# soth-core.net
KiCad netlist of a schematic drawn in EAGLE
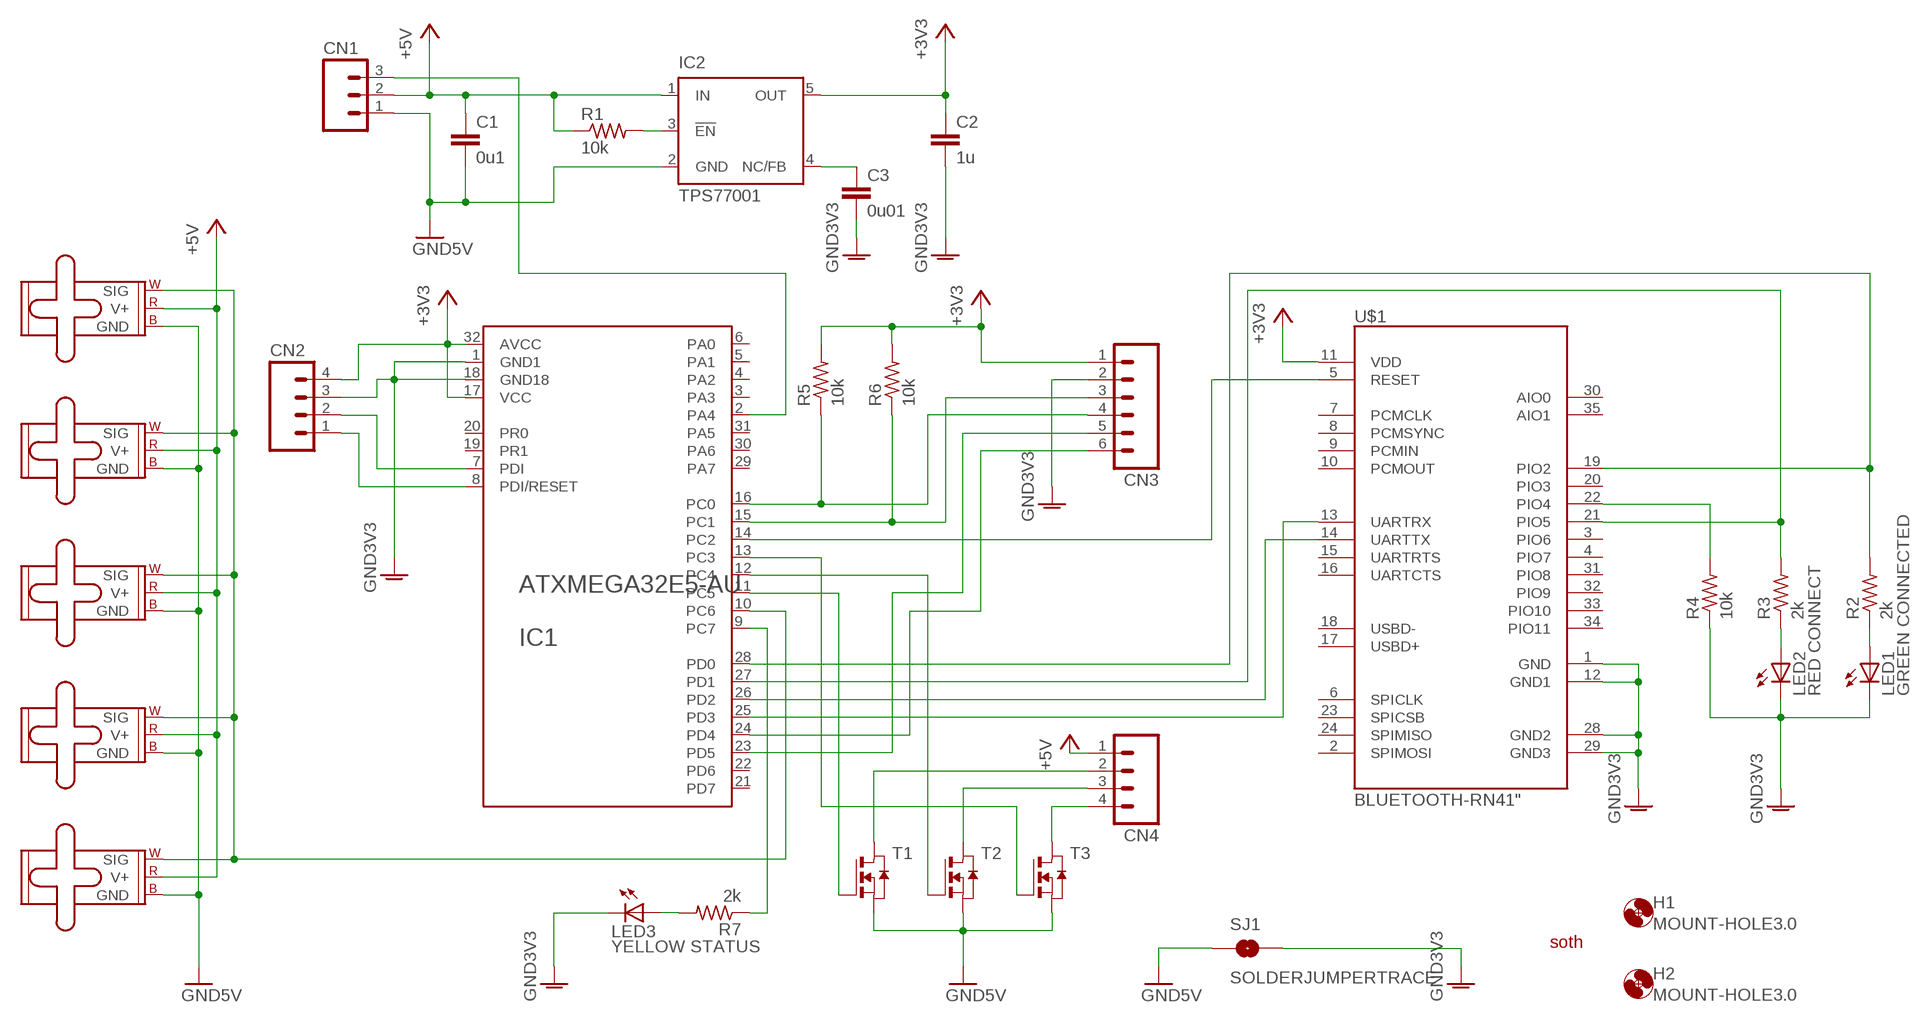
[diagram p0: schematic, sheet 1]

(export (version "E")
  (design (tool "Eeschema 10.0.6"))
  (components
    (comp (ref "C1")
      (value "0u1")
      (footprint "eagle-import:C1608")
      (libsource (lib "eagle-import") (part "C-EUC1608"))
    )
    (comp (ref "C2")
      (value "1u")
      (footprint "eagle-import:C1608")
      (libsource (lib "eagle-import") (part "C-EUC1608"))
    )
    (comp (ref "C3")
      (value "0u01")
      (footprint "eagle-import:C1608")
      (libsource (lib "eagle-import") (part "C-EUC1608"))
    )
    (comp (ref "CN1")
      (value "M03PTH")
      (footprint "eagle-import:1X03")
      (libsource (lib "eagle-import") (part "M03PTH"))
    )
    (comp (ref "CN2")
      (value "M04PTH")
      (footprint "eagle-import:1X04")
      (libsource (lib "eagle-import") (part "M04PTH"))
    )
    (comp (ref "CN3")
      (value "M06SILK_FEMALE_PTH")
      (footprint "eagle-import:1X06")
      (libsource (lib "eagle-import") (part "M06SILK_FEMALE_PTH"))
    )
    (comp (ref "CN4")
      (value "M04PTH")
      (footprint "eagle-import:1X04")
      (libsource (lib "eagle-import") (part "M04PTH"))
    )
    (comp (ref "H1")
      (value "MOUNT-HOLE3.0")
      (footprint "eagle-import:3,0")
      (libsource (lib "eagle-import") (part "MOUNT-HOLE3.0"))
    )
    (comp (ref "H2")
      (value "MOUNT-HOLE3.0")
      (footprint "eagle-import:3,0")
      (libsource (lib "eagle-import") (part "MOUNT-HOLE3.0"))
    )
    (comp (ref "IC1")
      (value "ATXMEGA32E5-AU")
      (footprint "eagle-import:TQFP32-08")
      (libsource (lib "eagle-import") (part "ATXMEGA32E5/16E5/8E5ATXMEGA32E5-AU"))
    )
    (comp (ref "IC2")
      (value "TPS77001")
      (footprint "eagle-import:SOT23-DBV")
      (fields (field (name "MF") "TEXAS INSTRUMENTS") (field (name "MPN") "TPS77001DBVT"))
      (libsource (lib "eagle-import") (part "TPS77001"))
    )
    (comp (ref "LED1")
      (value "GREEN CONNECTED")
      (footprint "eagle-import:CHIPLED_1206")
      (libsource (lib "eagle-import") (part "LEDCHIPLED_1206"))
    )
    (comp (ref "LED2")
      (value "RED CONNECT")
      (footprint "eagle-import:CHIPLED_1206")
      (libsource (lib "eagle-import") (part "LEDCHIPLED_1206"))
    )
    (comp (ref "LED3")
      (value "YELLOW STATUS")
      (footprint "eagle-import:CHIPLED_1206")
      (libsource (lib "eagle-import") (part "LEDCHIPLED_1206"))
    )
    (comp (ref "M1")
      (value "SMALL_SERVO")
      (footprint "eagle-import:1X03")
      (libsource (lib "eagle-import") (part "SMALL_SERVO"))
    )
    (comp (ref "M2")
      (value "SMALL_SERVO")
      (footprint "eagle-import:1X03")
      (libsource (lib "eagle-import") (part "SMALL_SERVO"))
    )
    (comp (ref "M3")
      (value "SMALL_SERVO")
      (footprint "eagle-import:1X03")
      (libsource (lib "eagle-import") (part "SMALL_SERVO"))
    )
    (comp (ref "M4")
      (value "SMALL_SERVO")
      (footprint "eagle-import:1X03")
      (libsource (lib "eagle-import") (part "SMALL_SERVO"))
    )
    (comp (ref "M5")
      (value "SMALL_SERVO")
      (footprint "eagle-import:1X03")
      (libsource (lib "eagle-import") (part "SMALL_SERVO"))
    )
    (comp (ref "R1")
      (value "10k")
      (footprint "eagle-import:R0603")
      (libsource (lib "eagle-import") (part "R-US_R0603"))
    )
    (comp (ref "R2")
      (value "2k")
      (footprint "eagle-import:R0603")
      (libsource (lib "eagle-import") (part "R-US_R0603"))
    )
    (comp (ref "R3")
      (value "2k")
      (footprint "eagle-import:R0603")
      (libsource (lib "eagle-import") (part "R-US_R0603"))
    )
    (comp (ref "R4")
      (value "10k")
      (footprint "eagle-import:R0603")
      (libsource (lib "eagle-import") (part "R-US_R0603"))
    )
    (comp (ref "R5")
      (value "10k")
      (footprint "eagle-import:R0603")
      (libsource (lib "eagle-import") (part "R-US_R0603"))
    )
    (comp (ref "R6")
      (value "10k")
      (footprint "eagle-import:R0603")
      (libsource (lib "eagle-import") (part "R-US_R0603"))
    )
    (comp (ref "R7")
      (value "2k")
      (footprint "eagle-import:R0603")
      (libsource (lib "eagle-import") (part "R-US_R0603"))
    )
    (comp (ref "SJ1")
      (value "SOLDERJUMPERTRACE")
      (footprint "eagle-import:SJ_2S-TRACE")
      (libsource (lib "eagle-import") (part "SOLDERJUMPERTRACE"))
    )
    (comp (ref "T1")
      (value "NMOSSOT23")
      (footprint "eagle-import:SOT-23")
      (libsource (lib "eagle-import") (part "NMOSSOT23"))
    )
    (comp (ref "T2")
      (value "NMOSSOT23")
      (footprint "eagle-import:SOT-23")
      (libsource (lib "eagle-import") (part "NMOSSOT23"))
    )
    (comp (ref "T3")
      (value "NMOSSOT23")
      (footprint "eagle-import:SOT-23")
      (libsource (lib "eagle-import") (part "NMOSSOT23"))
    )
    (comp (ref "U$1")
      (value "BLUETOOTH-RN41\"")
      (footprint "eagle-import:RN41")
      (libsource (lib "eagle-import") (part "BLUETOOTH-RN41{dblquote}"))
    )
    (comp (ref "U$2")
      (value "SOTH_LOGO")
      (footprint "eagle-import:SILK_LOGO")
      (libsource (lib "eagle-import") (part "SOTH_LOGO"))
    )
  )
  (nets
    (net (code "1") (name "+3V3") (class "Default")
      (node (ref "C2") (pin "1") (pinfunction "1_1") (pintype "passive"))
      (node (ref "CN2") (pin "4") (pinfunction "4_4") (pintype "passive"))
      (node (ref "CN3") (pin "1") (pinfunction "1_1") (pintype "passive"))
      (node (ref "IC1") (pin "17") (pinfunction "VCC_17") (pintype "power_in"))
      (node (ref "IC1") (pin "32") (pinfunction "AVCC_32") (pintype "power_in"))
      (node (ref "IC2") (pin "5") (pinfunction "OUT_5") (pintype "passive"))
      (node (ref "R5") (pin "2") (pinfunction "2_2") (pintype "passive"))
      (node (ref "R6") (pin "2") (pinfunction "2_2") (pintype "passive"))
      (node (ref "U$1") (pin "11") (pinfunction "VDD_11") (pintype "bidirectional"))
    )
    (net (code "2") (name "+5V") (class "Default")
      (node (ref "C1") (pin "1") (pinfunction "1_1") (pintype "passive"))
      (node (ref "CN1") (pin "2") (pinfunction "2_2") (pintype "passive"))
      (node (ref "CN4") (pin "1") (pinfunction "1_1") (pintype "passive"))
      (node (ref "IC2") (pin "1") (pinfunction "IN_1") (pintype "input"))
      (node (ref "M1") (pin "2") (pinfunction "V+_2") (pintype "bidirectional"))
      (node (ref "M2") (pin "2") (pinfunction "V+_2") (pintype "bidirectional"))
      (node (ref "M3") (pin "2") (pinfunction "V+_2") (pintype "bidirectional"))
      (node (ref "M4") (pin "2") (pinfunction "V+_2") (pintype "bidirectional"))
      (node (ref "M5") (pin "2") (pinfunction "V+_2") (pintype "bidirectional"))
      (node (ref "R1") (pin "1") (pinfunction "1_1") (pintype "passive"))
    )
    (net (code "3") (name "GND3V3") (class "Default")
      (node (ref "C2") (pin "2") (pinfunction "2_2") (pintype "passive"))
      (node (ref "C3") (pin "2") (pinfunction "2_2") (pintype "passive"))
      (node (ref "CN2") (pin "3") (pinfunction "3_3") (pintype "passive"))
      (node (ref "CN3") (pin "2") (pinfunction "2_2") (pintype "passive"))
      (node (ref "IC1") (pin "1") (pinfunction "GND1_1") (pintype "power_in"))
      (node (ref "IC1") (pin "18") (pinfunction "GND18_18") (pintype "power_in"))
      (node (ref "LED1") (pin "C") (pinfunction "C_C") (pintype "passive"))
      (node (ref "LED2") (pin "C") (pinfunction "C_C") (pintype "passive"))
      (node (ref "LED3") (pin "C") (pinfunction "C_C") (pintype "passive"))
      (node (ref "R4") (pin "1") (pinfunction "1_1") (pintype "passive"))
      (node (ref "SJ1") (pin "2") (pinfunction "2_2") (pintype "passive"))
      (node (ref "U$1") (pin "1") (pinfunction "GND_1") (pintype "bidirectional"))
      (node (ref "U$1") (pin "12") (pinfunction "GND1_12") (pintype "bidirectional"))
      (node (ref "U$1") (pin "28") (pinfunction "GND2_28") (pintype "bidirectional"))
      (node (ref "U$1") (pin "29") (pinfunction "GND3_29") (pintype "bidirectional"))
    )
    (net (code "4") (name "GND5V") (class "Default")
      (node (ref "C1") (pin "2") (pinfunction "2_2") (pintype "passive"))
      (node (ref "CN1") (pin "1") (pinfunction "1_1") (pintype "passive"))
      (node (ref "IC2") (pin "2") (pinfunction "GND_2") (pintype "power_in"))
      (node (ref "M1") (pin "3") (pinfunction "GND_3") (pintype "bidirectional"))
      (node (ref "M2") (pin "3") (pinfunction "GND_3") (pintype "bidirectional"))
      (node (ref "M3") (pin "3") (pinfunction "GND_3") (pintype "bidirectional"))
      (node (ref "M4") (pin "3") (pinfunction "GND_3") (pintype "bidirectional"))
      (node (ref "M5") (pin "3") (pinfunction "GND_3") (pintype "bidirectional"))
      (node (ref "SJ1") (pin "1") (pinfunction "1_1") (pintype "passive"))
      (node (ref "T1") (pin "2") (pinfunction "S_2") (pintype "passive"))
      (node (ref "T2") (pin "2") (pinfunction "S_2") (pintype "passive"))
      (node (ref "T3") (pin "2") (pinfunction "S_2") (pintype "passive"))
    )
    (net (code "5") (name "Net-(IC1-PA4)") (class "Default")
      (node (ref "CN1") (pin "3") (pinfunction "3_3") (pintype "passive"))
      (node (ref "IC1") (pin "2") (pinfunction "PA4_2") (pintype "bidirectional"))
    )
    (net (code "6") (name "Net-(IC1-PC0)") (class "Default")
      (node (ref "CN3") (pin "4") (pinfunction "4_4") (pintype "passive"))
      (node (ref "IC1") (pin "16") (pinfunction "PC0_16") (pintype "bidirectional"))
      (node (ref "R5") (pin "1") (pinfunction "1_1") (pintype "passive"))
    )
    (net (code "7") (name "Net-(IC1-PC1)") (class "Default")
      (node (ref "CN3") (pin "3") (pinfunction "3_3") (pintype "passive"))
      (node (ref "IC1") (pin "15") (pinfunction "PC1_15") (pintype "bidirectional"))
      (node (ref "R6") (pin "1") (pinfunction "1_1") (pintype "passive"))
    )
    (net (code "8") (name "Net-(IC1-PC2)") (class "Default")
      (node (ref "IC1") (pin "14") (pinfunction "PC2_14") (pintype "bidirectional"))
      (node (ref "U$1") (pin "5") (pinfunction "RESET_5") (pintype "bidirectional"))
    )
    (net (code "9") (name "Net-(IC1-PC3)") (class "Default")
      (node (ref "IC1") (pin "13") (pinfunction "PC3_13") (pintype "bidirectional"))
      (node (ref "T3") (pin "3") (pinfunction "G_3") (pintype "passive"))
    )
    (net (code "10") (name "Net-(IC1-PC4)") (class "Default")
      (node (ref "IC1") (pin "12") (pinfunction "PC4_12") (pintype "bidirectional"))
      (node (ref "T2") (pin "3") (pinfunction "G_3") (pintype "passive"))
    )
    (net (code "11") (name "Net-(IC1-PC5)") (class "Default")
      (node (ref "IC1") (pin "11") (pinfunction "PC5_11") (pintype "bidirectional"))
      (node (ref "T1") (pin "3") (pinfunction "G_3") (pintype "passive"))
    )
    (net (code "12") (name "Net-(IC1-PC6)") (class "Default")
      (node (ref "IC1") (pin "10") (pinfunction "PC6_10") (pintype "bidirectional"))
      (node (ref "M1") (pin "1") (pinfunction "SIG_1") (pintype "bidirectional"))
      (node (ref "M2") (pin "1") (pinfunction "SIG_1") (pintype "bidirectional"))
      (node (ref "M3") (pin "1") (pinfunction "SIG_1") (pintype "bidirectional"))
      (node (ref "M4") (pin "1") (pinfunction "SIG_1") (pintype "bidirectional"))
      (node (ref "M5") (pin "1") (pinfunction "SIG_1") (pintype "bidirectional"))
    )
    (net (code "13") (name "Net-(IC1-PC7)") (class "Default")
      (node (ref "IC1") (pin "9") (pinfunction "PC7_9") (pintype "bidirectional"))
      (node (ref "R7") (pin "1") (pinfunction "1_1") (pintype "passive"))
    )
    (net (code "14") (name "Net-(IC1-PD0)") (class "Default")
      (node (ref "IC1") (pin "28") (pinfunction "PD0_28") (pintype "bidirectional"))
      (node (ref "R2") (pin "2") (pinfunction "2_2") (pintype "passive"))
      (node (ref "U$1") (pin "19") (pinfunction "PIO2_19") (pintype "bidirectional"))
    )
    (net (code "15") (name "Net-(IC1-PD1)") (class "Default")
      (node (ref "IC1") (pin "27") (pinfunction "PD1_27") (pintype "bidirectional"))
      (node (ref "R3") (pin "2") (pinfunction "2_2") (pintype "passive"))
      (node (ref "U$1") (pin "21") (pinfunction "PIO5_21") (pintype "bidirectional"))
    )
    (net (code "16") (name "Net-(IC1-PD2)") (class "Default")
      (node (ref "IC1") (pin "26") (pinfunction "PD2_26") (pintype "bidirectional"))
      (node (ref "U$1") (pin "14") (pinfunction "UARTTX_14") (pintype "bidirectional"))
    )
    (net (code "17") (name "Net-(IC1-PD3)") (class "Default")
      (node (ref "IC1") (pin "25") (pinfunction "PD3_25") (pintype "bidirectional"))
      (node (ref "U$1") (pin "13") (pinfunction "UARTRX_13") (pintype "bidirectional"))
    )
    (net (code "18") (name "Net-(IC1-PD4)") (class "Default")
      (node (ref "CN3") (pin "6") (pinfunction "6_6") (pintype "passive"))
      (node (ref "IC1") (pin "24") (pinfunction "PD4_24") (pintype "bidirectional"))
    )
    (net (code "19") (name "Net-(IC1-PD5)") (class "Default")
      (node (ref "CN3") (pin "5") (pinfunction "5_5") (pintype "passive"))
      (node (ref "IC1") (pin "23") (pinfunction "PD5_23") (pintype "bidirectional"))
    )
    (net (code "20") (name "Net-(IC1-PDI)") (class "Default")
      (node (ref "CN2") (pin "2") (pinfunction "2_2") (pintype "passive"))
      (node (ref "IC1") (pin "7") (pinfunction "PDI_7") (pintype "bidirectional"))
    )
    (net (code "21") (name "Net-(IC1-PDI{slash}RESET)") (class "Default")
      (node (ref "CN2") (pin "1") (pinfunction "1_1") (pintype "passive"))
      (node (ref "IC1") (pin "8") (pinfunction "PDI/RESET_8") (pintype "bidirectional"))
    )
    (net (code "22") (name "Net-(IC2-NC{slash}FB)") (class "Default")
      (node (ref "C3") (pin "1") (pinfunction "1_1") (pintype "passive"))
      (node (ref "IC2") (pin "4") (pinfunction "NC/FB_4") (pintype "passive"))
    )
    (net (code "23") (name "Net-(IC2-~{EN})") (class "Default")
      (node (ref "IC2") (pin "3") (pinfunction "~{EN}_3") (pintype "input"))
      (node (ref "R1") (pin "2") (pinfunction "2_2") (pintype "passive"))
    )
    (net (code "24") (name "Net-(LED1-PadA)") (class "Default")
      (node (ref "LED1") (pin "A") (pinfunction "A_A") (pintype "passive"))
      (node (ref "R2") (pin "1") (pinfunction "1_1") (pintype "passive"))
    )
    (net (code "25") (name "Net-(LED2-PadA)") (class "Default")
      (node (ref "LED2") (pin "A") (pinfunction "A_A") (pintype "passive"))
      (node (ref "R3") (pin "1") (pinfunction "1_1") (pintype "passive"))
    )
    (net (code "26") (name "Net-(LED3-PadA)") (class "Default")
      (node (ref "LED3") (pin "A") (pinfunction "A_A") (pintype "passive"))
      (node (ref "R7") (pin "2") (pinfunction "2_2") (pintype "passive"))
    )
    (net (code "27") (name "Net-(T1-D)") (class "Default")
      (node (ref "CN4") (pin "2") (pinfunction "2_2") (pintype "passive"))
      (node (ref "T1") (pin "1") (pinfunction "D_1") (pintype "passive"))
    )
    (net (code "28") (name "Net-(T2-D)") (class "Default")
      (node (ref "CN4") (pin "3") (pinfunction "3_3") (pintype "passive"))
      (node (ref "T2") (pin "1") (pinfunction "D_1") (pintype "passive"))
    )
    (net (code "29") (name "Net-(T3-D)") (class "Default")
      (node (ref "CN4") (pin "4") (pinfunction "4_4") (pintype "passive"))
      (node (ref "T3") (pin "1") (pinfunction "D_1") (pintype "passive"))
    )
    (net (code "30") (name "Net-(U$1-PIO4)") (class "Default")
      (node (ref "R4") (pin "2") (pinfunction "2_2") (pintype "passive"))
      (node (ref "U$1") (pin "22") (pinfunction "PIO4_22") (pintype "bidirectional"))
    )
    (net (code "31") (name "unconnected-(IC1-PA0-Pad6)") (class "Default")
      (node (ref "IC1") (pin "6") (pinfunction "PA0_6") (pintype "bidirectional"))
    )
    (net (code "32") (name "unconnected-(IC1-PA1-Pad5)") (class "Default")
      (node (ref "IC1") (pin "5") (pinfunction "PA1_5") (pintype "bidirectional"))
    )
    (net (code "33") (name "unconnected-(IC1-PA2-Pad4)") (class "Default")
      (node (ref "IC1") (pin "4") (pinfunction "PA2_4") (pintype "bidirectional"))
    )
    (net (code "34") (name "unconnected-(IC1-PA3-Pad3)") (class "Default")
      (node (ref "IC1") (pin "3") (pinfunction "PA3_3") (pintype "bidirectional"))
    )
    (net (code "35") (name "unconnected-(IC1-PA5-Pad31)") (class "Default")
      (node (ref "IC1") (pin "31") (pinfunction "PA5_31") (pintype "bidirectional"))
    )
    (net (code "36") (name "unconnected-(IC1-PA6-Pad30)") (class "Default")
      (node (ref "IC1") (pin "30") (pinfunction "PA6_30") (pintype "bidirectional"))
    )
    (net (code "37") (name "unconnected-(IC1-PA7-Pad29)") (class "Default")
      (node (ref "IC1") (pin "29") (pinfunction "PA7_29") (pintype "bidirectional"))
    )
    (net (code "38") (name "unconnected-(IC1-PD6-Pad22)") (class "Default")
      (node (ref "IC1") (pin "22") (pinfunction "PD6_22") (pintype "bidirectional"))
    )
    (net (code "39") (name "unconnected-(IC1-PD7-Pad21)") (class "Default")
      (node (ref "IC1") (pin "21") (pinfunction "PD7_21") (pintype "bidirectional"))
    )
    (net (code "40") (name "unconnected-(IC1-PR0-Pad20)") (class "Default")
      (node (ref "IC1") (pin "20") (pinfunction "PR0_20") (pintype "bidirectional"))
    )
    (net (code "41") (name "unconnected-(IC1-PR1-Pad19)") (class "Default")
      (node (ref "IC1") (pin "19") (pinfunction "PR1_19") (pintype "bidirectional"))
    )
    (net (code "42") (name "unconnected-(U$1-AIO0-Pad30)") (class "Default")
      (node (ref "U$1") (pin "30") (pinfunction "AIO0_30") (pintype "bidirectional"))
    )
    (net (code "43") (name "unconnected-(U$1-AIO1-Pad35)") (class "Default")
      (node (ref "U$1") (pin "35") (pinfunction "AIO1_35") (pintype "bidirectional"))
    )
    (net (code "44") (name "unconnected-(U$1-PCMCLK-Pad7)") (class "Default")
      (node (ref "U$1") (pin "7") (pinfunction "PCMCLK_7") (pintype "bidirectional"))
    )
    (net (code "45") (name "unconnected-(U$1-PCMIN-Pad9)") (class "Default")
      (node (ref "U$1") (pin "9") (pinfunction "PCMIN_9") (pintype "bidirectional"))
    )
    (net (code "46") (name "unconnected-(U$1-PCMOUT-Pad10)") (class "Default")
      (node (ref "U$1") (pin "10") (pinfunction "PCMOUT_10") (pintype "bidirectional"))
    )
    (net (code "47") (name "unconnected-(U$1-PCMSYNC-Pad8)") (class "Default")
      (node (ref "U$1") (pin "8") (pinfunction "PCMSYNC_8") (pintype "bidirectional"))
    )
    (net (code "48") (name "unconnected-(U$1-PIO3-Pad20)") (class "Default")
      (node (ref "U$1") (pin "20") (pinfunction "PIO3_20") (pintype "bidirectional"))
    )
    (net (code "49") (name "unconnected-(U$1-PIO6-Pad3)") (class "Default")
      (node (ref "U$1") (pin "3") (pinfunction "PIO6_3") (pintype "bidirectional"))
    )
    (net (code "50") (name "unconnected-(U$1-PIO7-Pad4)") (class "Default")
      (node (ref "U$1") (pin "4") (pinfunction "PIO7_4") (pintype "bidirectional"))
    )
    (net (code "51") (name "unconnected-(U$1-PIO8-Pad31)") (class "Default")
      (node (ref "U$1") (pin "31") (pinfunction "PIO8_31") (pintype "bidirectional"))
    )
    (net (code "52") (name "unconnected-(U$1-PIO9-Pad32)") (class "Default")
      (node (ref "U$1") (pin "32") (pinfunction "PIO9_32") (pintype "bidirectional"))
    )
    (net (code "53") (name "unconnected-(U$1-PIO10-Pad33)") (class "Default")
      (node (ref "U$1") (pin "33") (pinfunction "PIO10_33") (pintype "bidirectional"))
    )
    (net (code "54") (name "unconnected-(U$1-PIO11-Pad34)") (class "Default")
      (node (ref "U$1") (pin "34") (pinfunction "PIO11_34") (pintype "bidirectional"))
    )
    (net (code "55") (name "unconnected-(U$1-SPICLK-Pad6)") (class "Default")
      (node (ref "U$1") (pin "6") (pinfunction "SPICLK_6") (pintype "bidirectional"))
    )
    (net (code "56") (name "unconnected-(U$1-SPICSB-Pad23)") (class "Default")
      (node (ref "U$1") (pin "23") (pinfunction "SPICSB_23") (pintype "bidirectional"))
    )
    (net (code "57") (name "unconnected-(U$1-SPIMISO-Pad24)") (class "Default")
      (node (ref "U$1") (pin "24") (pinfunction "SPIMISO_24") (pintype "bidirectional"))
    )
    (net (code "58") (name "unconnected-(U$1-SPIMOSI-Pad2)") (class "Default")
      (node (ref "U$1") (pin "2") (pinfunction "SPIMOSI_2") (pintype "bidirectional"))
    )
    (net (code "59") (name "unconnected-(U$1-UARTCTS-Pad16)") (class "Default")
      (node (ref "U$1") (pin "16") (pinfunction "UARTCTS_16") (pintype "bidirectional"))
    )
    (net (code "60") (name "unconnected-(U$1-UARTRTS-Pad15)") (class "Default")
      (node (ref "U$1") (pin "15") (pinfunction "UARTRTS_15") (pintype "bidirectional"))
    )
    (net (code "61") (name "unconnected-(U$1-USBD+-Pad17)") (class "Default")
      (node (ref "U$1") (pin "17") (pinfunction "USBD+_17") (pintype "bidirectional"))
    )
    (net (code "62") (name "unconnected-(U$1-USBD--Pad18)") (class "Default")
      (node (ref "U$1") (pin "18") (pinfunction "USBD-_18") (pintype "bidirectional"))
    )
  )
)
